# ospi_v14.net
KiCad netlist of a schematic drawn in EAGLE
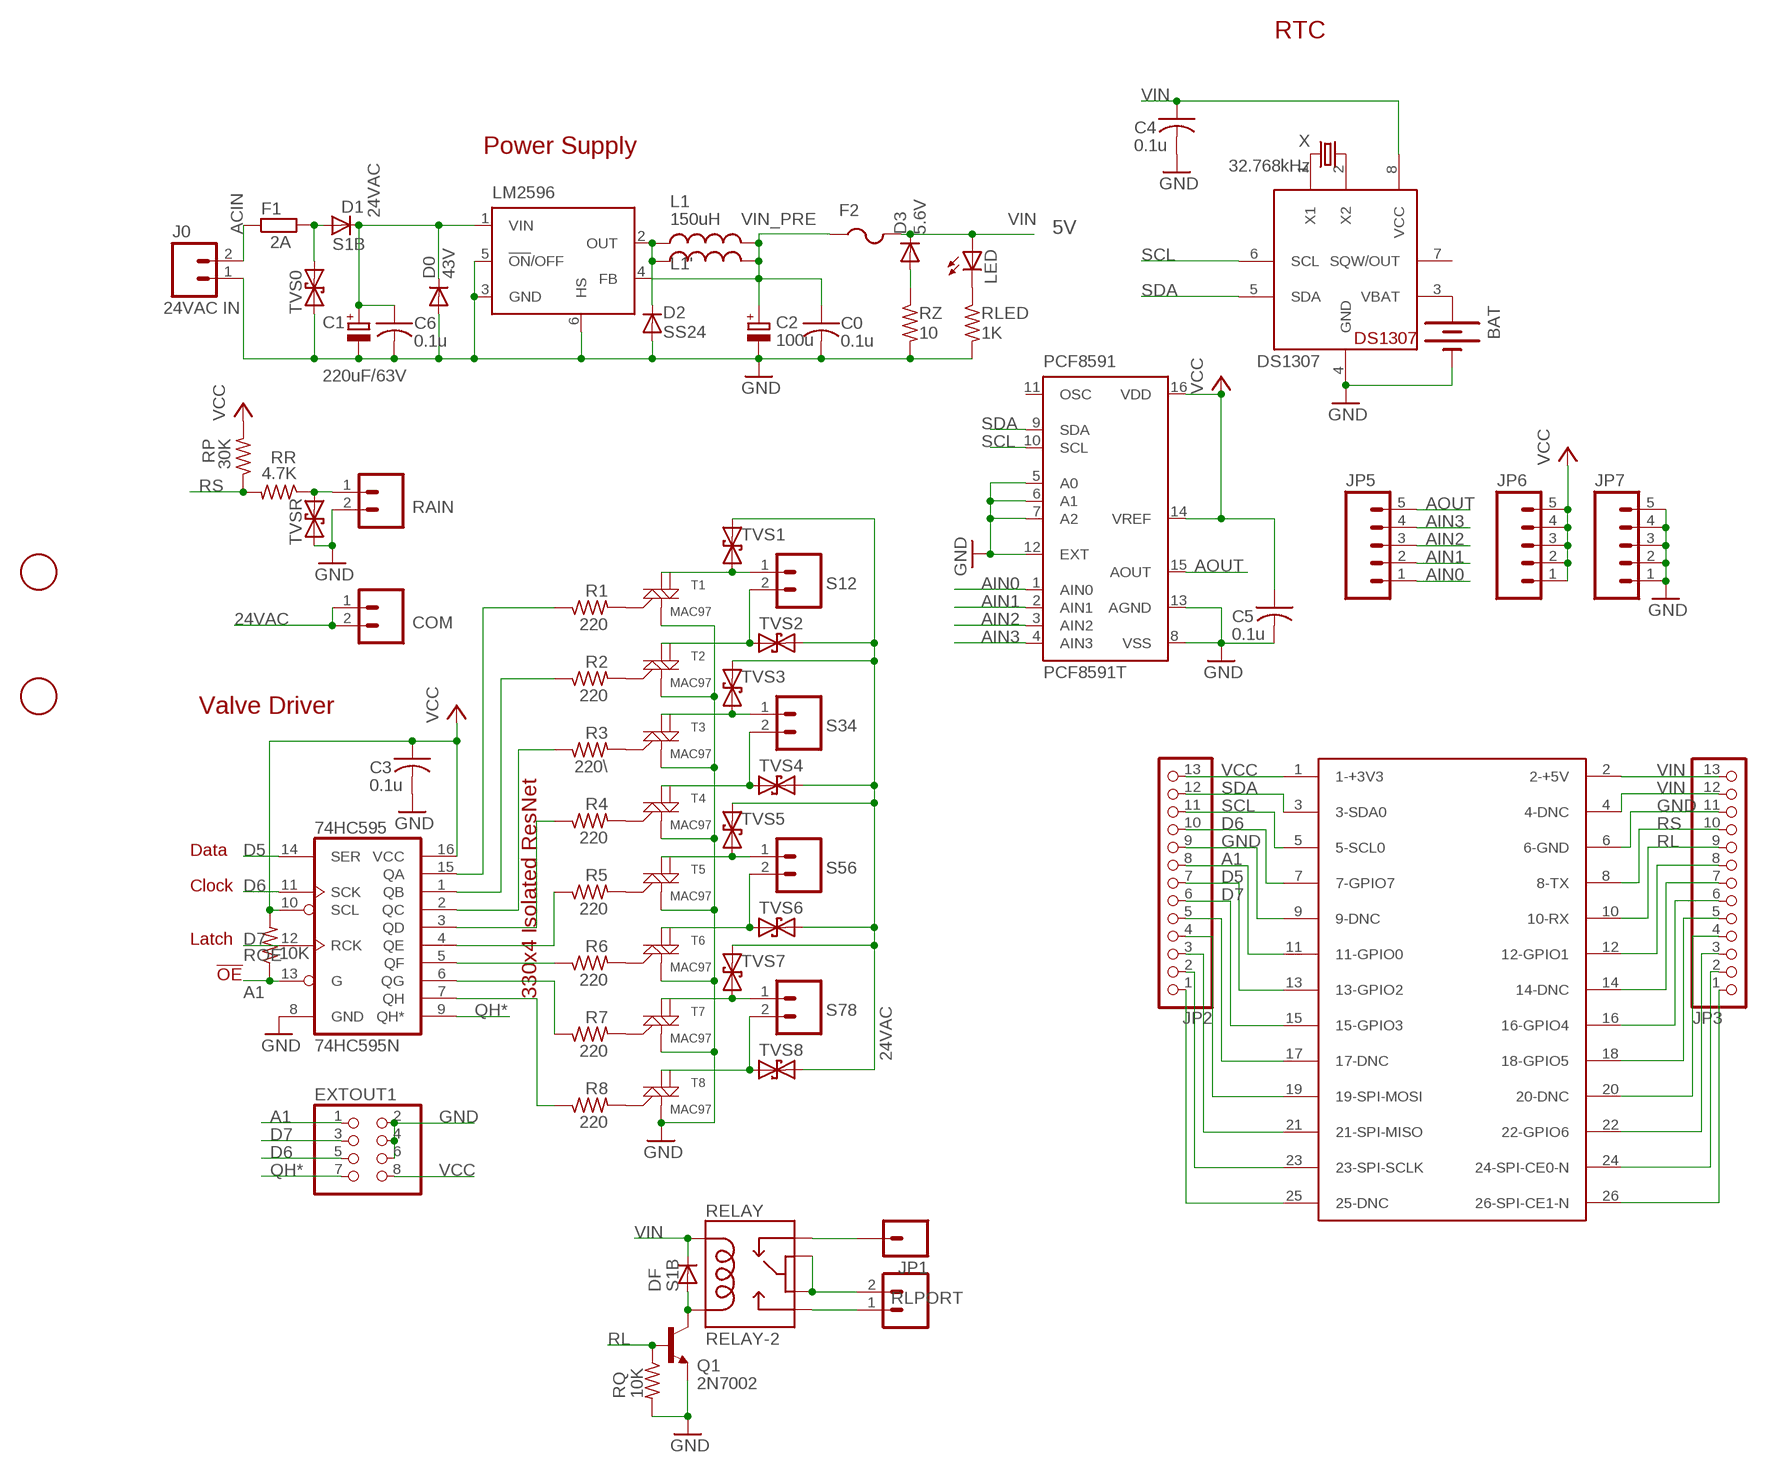
[diagram p0: schematic, sheet 1]

(export (version "E")
  (design (tool "Eeschema 10.0.6"))
  (components
    (comp (ref "74HC595")
      (value "74HC595N")
      (footprint "eagle-import:SO16")
      (libsource (lib "eagle-import") (part "74595DLS"))
    )
    (comp (ref "BAT")
      (value "BATTERYBATTERY_12MM_SMT")
      (footprint "eagle-import:BATTCON_12MM_SMT")
      (libsource (lib "eagle-import") (part "BATTERYBATTERY_12MM_SMT"))
    )
    (comp (ref "C0")
      (value "0.1u")
      (footprint "eagle-import:C0805K")
      (libsource (lib "eagle-import") (part "C-USC0805K"))
    )
    (comp (ref "C1")
      (value "220uF/63V")
      (footprint "eagle-import:E5-10,5")
      (libsource (lib "eagle-import") (part "CPOL-EUE5-10.5"))
    )
    (comp (ref "C2")
      (value "100u")
      (footprint "eagle-import:E3,5-8")
      (libsource (lib "eagle-import") (part "CPOL-EUE3.5-8"))
    )
    (comp (ref "C3")
      (value "0.1u")
      (footprint "eagle-import:C0805K")
      (libsource (lib "eagle-import") (part "C-USC0805K"))
    )
    (comp (ref "C4")
      (value "0.1u")
      (footprint "eagle-import:C0805K")
      (libsource (lib "eagle-import") (part "C-USC0805K"))
    )
    (comp (ref "C5")
      (value "0.1u")
      (footprint "eagle-import:C0805K")
      (libsource (lib "eagle-import") (part "C-USC0805K"))
    )
    (comp (ref "C6")
      (value "0.1u")
      (footprint "eagle-import:C0805K")
      (libsource (lib "eagle-import") (part "C-USC0805K"))
    )
    (comp (ref "COM")
      (value "M025MM-X")
      (footprint "eagle-import:SCREWTERMINAL-5MM-2-X")
      (libsource (lib "eagle-import") (part "M025MM-X"))
    )
    (comp (ref "D0")
      (value "43V")
      (footprint "eagle-import:MINIMELF")
      (libsource (lib "eagle-import") (part "DIODE-MINIMELF"))
    )
    (comp (ref "D1")
      (value "S1B")
      (footprint "eagle-import:DO-214AC")
      (libsource (lib "eagle-import") (part "DIODE-DO-214AC"))
    )
    (comp (ref "D2")
      (value "SS24")
      (footprint "eagle-import:SMB")
      (libsource (lib "eagle-import") (part "DIODE-SMB"))
    )
    (comp (ref "D3")
      (value "5.6V")
      (footprint "eagle-import:MINIMELF")
      (libsource (lib "eagle-import") (part "DIODE-MINIMELF"))
    )
    (comp (ref "DF")
      (value "S1B")
      (footprint "eagle-import:DO-214AC")
      (libsource (lib "eagle-import") (part "DIODE-DO-214AC"))
    )
    (comp (ref "DS1307")
      (value "DS1307")
      (footprint "eagle-import:SO08")
      (libsource (lib "eagle-import") (part "DS1307SOIC"))
    )
    (comp (ref "EXTOUT1")
      (value "PINHD-2X4/90")
      (footprint "eagle-import:2X04_90")
      (libsource (lib "eagle-import") (part "PINHD-2X4/90"))
    )
    (comp (ref "F1")
      (value "2A")
      (footprint "eagle-import:0411V")
      (libsource (lib "eagle-import") (part "R-EU_0411/3V"))
    )
    (comp (ref "F2")
      (value "PTCFUSE-1812")
      (footprint "eagle-import:1812")
      (libsource (lib "eagle-import") (part "PTCFUSE-1812"))
    )
    (comp (ref "J0")
      (value "24VAC IN")
      (footprint "eagle-import:SCREWTERMINAL-4MM-2-X")
      (libsource (lib "eagle-import") (part "M024MM-X"))
    )
    (comp (ref "JP1")
      (value "M01PTH")
      (footprint "eagle-import:1X01")
      (libsource (lib "eagle-import") (part "M01PTH"))
    )
    (comp (ref "JP2")
      (value "PINHD-1X13_BIG")
      (footprint "eagle-import:1X13-BIG")
      (libsource (lib "eagle-import") (part "PINHD-1X13_BIG"))
    )
    (comp (ref "JP3")
      (value "PINHD-1X13_BIG")
      (footprint "eagle-import:1X13-BIG")
      (libsource (lib "eagle-import") (part "PINHD-1X13_BIG"))
    )
    (comp (ref "JP5")
      (value "M05LOCK")
      (footprint "eagle-import:1X05_LOCK")
      (libsource (lib "eagle-import") (part "M05LOCK"))
    )
    (comp (ref "JP6")
      (value "M05LOCK")
      (footprint "eagle-import:1X05_LOCK")
      (libsource (lib "eagle-import") (part "M05LOCK"))
    )
    (comp (ref "JP7")
      (value "M05LOCK")
      (footprint "eagle-import:1X05_LOCK")
      (libsource (lib "eagle-import") (part "M05LOCK"))
    )
    (comp (ref "L1")
      (value "150uH")
      (footprint "eagle-import:CDRH125")
      (libsource (lib "eagle-import") (part "INDUCTORPWR"))
    )
    (comp (ref "L1'")
      (value "150uH")
      (footprint "eagle-import:0207_7")
      (libsource (lib "eagle-import") (part "L-US0207/7"))
    )
    (comp (ref "LED")
      (value "LEDCHIPLED_0805")
      (footprint "eagle-import:CHIPLED_0805")
      (libsource (lib "eagle-import") (part "LEDCHIPLED_0805"))
    )
    (comp (ref "LM2596")
      (value "LM2596S")
      (footprint "eagle-import:TO263-5")
      (fields (field (name "MF") "NATIONAL SEMICONDUCTOR") (field (name "MPN") "LM2596S-ADJ/NOPB"))
      (libsource (lib "eagle-import") (part "LM2596S"))
    )
    (comp (ref "PCF8591")
      (value "PCF8591T")
      (footprint "eagle-import:SO16W")
      (fields (field (name "MPN") "PCF8591T/2,512"))
      (libsource (lib "eagle-import") (part "PCF8591T"))
    )
    (comp (ref "Q1")
      (value "2N7002")
      (footprint "eagle-import:SOT23-3")
      (libsource (lib "eagle-import") (part "TRANSISTOR_NPNSOT23-3"))
    )
    (comp (ref "R1")
      (value "220")
      (footprint "eagle-import:R0805")
      (libsource (lib "eagle-import") (part "R-US_R0805"))
    )
    (comp (ref "R2")
      (value "220")
      (footprint "eagle-import:R0805")
      (libsource (lib "eagle-import") (part "R-US_R0805"))
    )
    (comp (ref "R3")
      (value "220\\")
      (footprint "eagle-import:R0805")
      (libsource (lib "eagle-import") (part "R-US_R0805"))
    )
    (comp (ref "R4")
      (value "220")
      (footprint "eagle-import:R0805")
      (libsource (lib "eagle-import") (part "R-US_R0805"))
    )
    (comp (ref "R5")
      (value "220")
      (footprint "eagle-import:R0805")
      (libsource (lib "eagle-import") (part "R-US_R0805"))
    )
    (comp (ref "R6")
      (value "220")
      (footprint "eagle-import:R0805")
      (libsource (lib "eagle-import") (part "R-US_R0805"))
    )
    (comp (ref "R7")
      (value "220")
      (footprint "eagle-import:R0805")
      (libsource (lib "eagle-import") (part "R-US_R0805"))
    )
    (comp (ref "R8")
      (value "220")
      (footprint "eagle-import:R0805")
      (libsource (lib "eagle-import") (part "R-US_R0805"))
    )
    (comp (ref "RAIN")
      (value "M025MM-X")
      (footprint "eagle-import:SCREWTERMINAL-5MM-2-X")
      (libsource (lib "eagle-import") (part "M025MM-X"))
    )
    (comp (ref "RELAY")
      (value "RELAY-2")
      (footprint "eagle-import:RELAY-HK4100F")
      (libsource (lib "eagle-import") (part "RELAY-2"))
    )
    (comp (ref "RLED")
      (value "1K")
      (footprint "eagle-import:R0805")
      (libsource (lib "eagle-import") (part "R-US_R0805"))
    )
    (comp (ref "RLPORT")
      (value "M025MM")
      (footprint "eagle-import:SCREWTERMINAL-5MM-2")
      (libsource (lib "eagle-import") (part "M025MM"))
    )
    (comp (ref "ROE")
      (value "10K")
      (footprint "eagle-import:R0805")
      (libsource (lib "eagle-import") (part "R-US_R0805"))
    )
    (comp (ref "RP")
      (value "30K")
      (footprint "eagle-import:R0805")
      (libsource (lib "eagle-import") (part "R-US_R0805"))
    )
    (comp (ref "RQ")
      (value "10K")
      (footprint "eagle-import:R0805")
      (libsource (lib "eagle-import") (part "R-US_R0805"))
    )
    (comp (ref "RR")
      (value "4.7K")
      (footprint "eagle-import:R0805")
      (libsource (lib "eagle-import") (part "R-US_R0805"))
    )
    (comp (ref "RZ")
      (value "10")
      (footprint "eagle-import:R0805")
      (libsource (lib "eagle-import") (part "R-US_R0805"))
    )
    (comp (ref "S12")
      (value "M025MM-X")
      (footprint "eagle-import:SCREWTERMINAL-5MM-2-X")
      (libsource (lib "eagle-import") (part "M025MM-X"))
    )
    (comp (ref "S34")
      (value "M025MM-X")
      (footprint "eagle-import:SCREWTERMINAL-5MM-2-X")
      (libsource (lib "eagle-import") (part "M025MM-X"))
    )
    (comp (ref "S56")
      (value "M025MM-X")
      (footprint "eagle-import:SCREWTERMINAL-5MM-2-X")
      (libsource (lib "eagle-import") (part "M025MM-X"))
    )
    (comp (ref "S78")
      (value "M025MM-X")
      (footprint "eagle-import:SCREWTERMINAL-5MM-2-X")
      (libsource (lib "eagle-import") (part "M025MM-X"))
    )
    (comp (ref "T1")
      (value "MAC97")
      (footprint "eagle-import:SOT223")
      (libsource (lib "eagle-import") (part "MAC97SOT223"))
    )
    (comp (ref "T2")
      (value "MAC97")
      (footprint "eagle-import:SOT223")
      (libsource (lib "eagle-import") (part "MAC97SOT223"))
    )
    (comp (ref "T3")
      (value "MAC97")
      (footprint "eagle-import:SOT223")
      (libsource (lib "eagle-import") (part "MAC97SOT223"))
    )
    (comp (ref "T4")
      (value "MAC97")
      (footprint "eagle-import:SOT223")
      (libsource (lib "eagle-import") (part "MAC97SOT223"))
    )
    (comp (ref "T5")
      (value "MAC97")
      (footprint "eagle-import:SOT223")
      (libsource (lib "eagle-import") (part "MAC97SOT223"))
    )
    (comp (ref "T6")
      (value "MAC97")
      (footprint "eagle-import:SOT223")
      (libsource (lib "eagle-import") (part "MAC97SOT223"))
    )
    (comp (ref "T7")
      (value "MAC97")
      (footprint "eagle-import:SOT223")
      (libsource (lib "eagle-import") (part "MAC97SOT223"))
    )
    (comp (ref "T8")
      (value "MAC97")
      (footprint "eagle-import:SOT223")
      (libsource (lib "eagle-import") (part "MAC97SOT223"))
    )
    (comp (ref "TVS0")
      (value "TVSSMB")
      (footprint "eagle-import:SMB")
      (libsource (lib "eagle-import") (part "TVSSMB"))
    )
    (comp (ref "TVS1")
      (value "TVSSMB")
      (footprint "eagle-import:SMB")
      (libsource (lib "eagle-import") (part "TVSSMB"))
    )
    (comp (ref "TVS2")
      (value "TVSSMB")
      (footprint "eagle-import:SMB")
      (libsource (lib "eagle-import") (part "TVSSMB"))
    )
    (comp (ref "TVS3")
      (value "TVSSMB")
      (footprint "eagle-import:SMB")
      (libsource (lib "eagle-import") (part "TVSSMB"))
    )
    (comp (ref "TVS4")
      (value "TVSSMB")
      (footprint "eagle-import:SMB")
      (libsource (lib "eagle-import") (part "TVSSMB"))
    )
    (comp (ref "TVS5")
      (value "TVSSMB")
      (footprint "eagle-import:SMB")
      (libsource (lib "eagle-import") (part "TVSSMB"))
    )
    (comp (ref "TVS6")
      (value "TVSSMB")
      (footprint "eagle-import:SMB")
      (libsource (lib "eagle-import") (part "TVSSMB"))
    )
    (comp (ref "TVS7")
      (value "TVSSMB")
      (footprint "eagle-import:SMB")
      (libsource (lib "eagle-import") (part "TVSSMB"))
    )
    (comp (ref "TVS8")
      (value "TVSSMB")
      (footprint "eagle-import:SMB")
      (libsource (lib "eagle-import") (part "TVSSMB"))
    )
    (comp (ref "TVSR")
      (value "TVSSMB")
      (footprint "eagle-import:SMB")
      (libsource (lib "eagle-import") (part "TVSSMB"))
    )
    (comp (ref "U$1")
      (value "FIDUCIAL")
      (footprint "eagle-import:FIDUCIAL_1MM")
      (libsource (lib "eagle-import") (part "FIDUCIAL"))
    )
    (comp (ref "U$2")
      (value "RASPBERRY-PI")
      (footprint "eagle-import:RASPBERRY-PI")
      (libsource (lib "eagle-import") (part "RASPBERRY-PI"))
    )
    (comp (ref "U$3")
      (value "FIDUCIAL")
      (footprint "eagle-import:FIDUCIAL_1MM")
      (libsource (lib "eagle-import") (part "FIDUCIAL"))
    )
    (comp (ref "X")
      (value "32.768kHz")
      (footprint "eagle-import:TC38H")
      (libsource (lib "eagle-import") (part "CRYSTALTC38H"))
    )
  )
  (nets
    (net (code "1") (name "/24VAC") (class "Default")
      (node (ref "COM") (pin "1") (pinfunction "1_1") (pintype "passive"))
      (node (ref "COM") (pin "2") (pinfunction "2_2") (pintype "passive"))
      (node (ref "D1") (pin "A") (pinfunction "A_A") (pintype "passive"))
      (node (ref "F1") (pin "2") (pinfunction "2_2") (pintype "passive"))
      (node (ref "TVS0") (pin "C") (pinfunction "C_C") (pintype "passive"))
      (node (ref "TVS1") (pin "C") (pinfunction "C_C") (pintype "passive"))
      (node (ref "TVS2") (pin "C") (pinfunction "C_C") (pintype "passive"))
      (node (ref "TVS3") (pin "C") (pinfunction "C_C") (pintype "passive"))
      (node (ref "TVS4") (pin "C") (pinfunction "C_C") (pintype "passive"))
      (node (ref "TVS5") (pin "C") (pinfunction "C_C") (pintype "passive"))
      (node (ref "TVS6") (pin "C") (pinfunction "C_C") (pintype "passive"))
      (node (ref "TVS7") (pin "C") (pinfunction "C_C") (pintype "passive"))
      (node (ref "TVS8") (pin "C") (pinfunction "C_C") (pintype "passive"))
    )
    (net (code "2") (name "/A1") (class "Default")
      (node (ref "74HC595") (pin "13") (pinfunction "G_13") (pintype "input"))
      (node (ref "EXTOUT1") (pin "1") (pinfunction "1_1") (pintype "passive"))
      (node (ref "JP2") (pin "8") (pinfunction "8_8") (pintype "passive"))
      (node (ref "ROE") (pin "1") (pinfunction "1_1") (pintype "passive"))
      (node (ref "U$2") (pin "11") (pinfunction "11-GPIO0_11") (pintype "bidirectional"))
    )
    (net (code "3") (name "/ACIN") (class "Default")
      (node (ref "F1") (pin "1") (pinfunction "1_1") (pintype "passive"))
      (node (ref "J0") (pin "2") (pinfunction "2_2") (pintype "passive"))
    )
    (net (code "4") (name "/AIN0") (class "Default")
      (node (ref "JP5") (pin "1") (pinfunction "1_1") (pintype "passive"))
      (node (ref "PCF8591") (pin "1") (pinfunction "AIN0_1") (pintype "input"))
    )
    (net (code "5") (name "/AIN1") (class "Default")
      (node (ref "JP5") (pin "2") (pinfunction "2_2") (pintype "passive"))
      (node (ref "PCF8591") (pin "2") (pinfunction "AIN1_2") (pintype "input"))
    )
    (net (code "6") (name "/AIN2") (class "Default")
      (node (ref "JP5") (pin "3") (pinfunction "3_3") (pintype "passive"))
      (node (ref "PCF8591") (pin "3") (pinfunction "AIN2_3") (pintype "input"))
    )
    (net (code "7") (name "/AIN3") (class "Default")
      (node (ref "JP5") (pin "4") (pinfunction "4_4") (pintype "passive"))
      (node (ref "PCF8591") (pin "4") (pinfunction "AIN3_4") (pintype "input"))
    )
    (net (code "8") (name "/AOUT") (class "Default")
      (node (ref "JP5") (pin "5") (pinfunction "5_5") (pintype "passive"))
      (node (ref "PCF8591") (pin "15") (pinfunction "AOUT_15") (pintype "output"))
    )
    (net (code "9") (name "/D5") (class "Default")
      (node (ref "74HC595") (pin "14") (pinfunction "SER_14") (pintype "input"))
      (node (ref "JP2") (pin "7") (pinfunction "7_7") (pintype "passive"))
      (node (ref "U$2") (pin "13") (pinfunction "13-GPIO2_13") (pintype "bidirectional"))
    )
    (net (code "10") (name "/D6") (class "Default")
      (node (ref "74HC595") (pin "11") (pinfunction "SCK_11") (pintype "input"))
      (node (ref "EXTOUT1") (pin "5") (pinfunction "5_5") (pintype "passive"))
      (node (ref "JP2") (pin "10") (pinfunction "10_10") (pintype "passive"))
      (node (ref "U$2") (pin "7") (pinfunction "7-GPIO7_7") (pintype "bidirectional"))
    )
    (net (code "11") (name "/D7") (class "Default")
      (node (ref "74HC595") (pin "12") (pinfunction "RCK_12") (pintype "input"))
      (node (ref "EXTOUT1") (pin "3") (pinfunction "3_3") (pintype "passive"))
      (node (ref "JP2") (pin "6") (pinfunction "6_6") (pintype "passive"))
      (node (ref "U$2") (pin "15") (pinfunction "15-GPIO3_15") (pintype "bidirectional"))
    )
    (net (code "12") (name "/QH*") (class "Default")
      (node (ref "74HC595") (pin "9") (pinfunction "QH*_9") (pintype "tri_state"))
      (node (ref "EXTOUT1") (pin "7") (pinfunction "7_7") (pintype "passive"))
    )
    (net (code "13") (name "/RL") (class "Default")
      (node (ref "JP3") (pin "9") (pinfunction "9_9") (pintype "passive"))
      (node (ref "Q1") (pin "1") (pinfunction "B_1") (pintype "passive"))
      (node (ref "RQ") (pin "1") (pinfunction "1_1") (pintype "passive"))
      (node (ref "U$2") (pin "10") (pinfunction "10-RX_10") (pintype "bidirectional"))
    )
    (net (code "14") (name "/RS") (class "Default")
      (node (ref "JP3") (pin "10") (pinfunction "10_10") (pintype "passive"))
      (node (ref "RP") (pin "1") (pinfunction "1_1") (pintype "passive"))
      (node (ref "RR") (pin "2") (pinfunction "2_2") (pintype "passive"))
      (node (ref "U$2") (pin "8") (pinfunction "8-TX_8") (pintype "bidirectional"))
    )
    (net (code "15") (name "/SCL") (class "Default")
      (node (ref "DS1307") (pin "6") (pinfunction "SCL_6") (pintype "bidirectional"))
      (node (ref "JP2") (pin "11") (pinfunction "11_11") (pintype "passive"))
      (node (ref "PCF8591") (pin "10") (pinfunction "SCL_10") (pintype "input"))
      (node (ref "U$2") (pin "5") (pinfunction "5-SCL0_5") (pintype "bidirectional"))
    )
    (net (code "16") (name "/SDA") (class "Default")
      (node (ref "DS1307") (pin "5") (pinfunction "SDA_5") (pintype "bidirectional"))
      (node (ref "JP2") (pin "12") (pinfunction "12_12") (pintype "passive"))
      (node (ref "PCF8591") (pin "9") (pinfunction "SDA_9") (pintype "bidirectional"))
      (node (ref "U$2") (pin "3") (pinfunction "3-SDA0_3") (pintype "bidirectional"))
    )
    (net (code "17") (name "/VIN") (class "Default")
      (node (ref "C4") (pin "1") (pinfunction "1_1") (pintype "passive"))
      (node (ref "D3") (pin "C") (pinfunction "C_C") (pintype "passive"))
      (node (ref "DF") (pin "C") (pinfunction "C_C") (pintype "passive"))
      (node (ref "DS1307") (pin "8") (pinfunction "VCC_8") (pintype "power_in"))
      (node (ref "F2") (pin "2") (pinfunction "2_2") (pintype "passive"))
      (node (ref "JP3") (pin "12") (pinfunction "12_12") (pintype "passive"))
      (node (ref "JP3") (pin "13") (pinfunction "13_13") (pintype "passive"))
      (node (ref "LED") (pin "A") (pinfunction "A_A") (pintype "passive"))
      (node (ref "RELAY") (pin "2") (pinfunction "2_2") (pintype "bidirectional"))
      (node (ref "U$2") (pin "2") (pinfunction "2-+5V_2") (pintype "bidirectional"))
      (node (ref "U$2") (pin "4") (pinfunction "4-DNC_4") (pintype "bidirectional"))
    )
    (net (code "18") (name "/VIN_PRE") (class "Default")
      (node (ref "C0") (pin "1") (pinfunction "1_1") (pintype "passive"))
      (node (ref "C2") (pin "+") (pinfunction "+_+") (pintype "passive"))
      (node (ref "F2") (pin "1") (pinfunction "1_1") (pintype "passive"))
      (node (ref "L1") (pin "2") (pinfunction "2_2") (pintype "passive"))
      (node (ref "L1'") (pin "2") (pinfunction "2_2") (pintype "passive"))
      (node (ref "LM2596") (pin "4") (pinfunction "FB_4") (pintype "input"))
    )
    (net (code "19") (name "GND") (class "Default")
      (node (ref "74HC595") (pin "8") (pinfunction "GND_8") (pintype "power_in"))
      (node (ref "BAT") (pin "P$1") (pinfunction "-_P$1") (pintype "power_in"))
      (node (ref "C0") (pin "2") (pinfunction "2_2") (pintype "passive"))
      (node (ref "C1") (pin "-") (pinfunction "-_-") (pintype "passive"))
      (node (ref "C2") (pin "-") (pinfunction "-_-") (pintype "passive"))
      (node (ref "C3") (pin "2") (pinfunction "2_2") (pintype "passive"))
      (node (ref "C4") (pin "2") (pinfunction "2_2") (pintype "passive"))
      (node (ref "C5") (pin "2") (pinfunction "2_2") (pintype "passive"))
      (node (ref "C6") (pin "2") (pinfunction "2_2") (pintype "passive"))
      (node (ref "D0") (pin "A") (pinfunction "A_A") (pintype "passive"))
      (node (ref "D2") (pin "A") (pinfunction "A_A") (pintype "passive"))
      (node (ref "DS1307") (pin "4") (pinfunction "GND_4") (pintype "power_in"))
      (node (ref "EXTOUT1") (pin "2") (pinfunction "2_2") (pintype "passive"))
      (node (ref "EXTOUT1") (pin "4") (pinfunction "4_4") (pintype "passive"))
      (node (ref "EXTOUT1") (pin "6") (pinfunction "6_6") (pintype "passive"))
      (node (ref "J0") (pin "1") (pinfunction "1_1") (pintype "passive"))
      (node (ref "JP2") (pin "9") (pinfunction "9_9") (pintype "passive"))
      (node (ref "JP3") (pin "11") (pinfunction "11_11") (pintype "passive"))
      (node (ref "JP7") (pin "1") (pinfunction "1_1") (pintype "passive"))
      (node (ref "JP7") (pin "2") (pinfunction "2_2") (pintype "passive"))
      (node (ref "JP7") (pin "3") (pinfunction "3_3") (pintype "passive"))
      (node (ref "JP7") (pin "4") (pinfunction "4_4") (pintype "passive"))
      (node (ref "JP7") (pin "5") (pinfunction "5_5") (pintype "passive"))
      (node (ref "LM2596") (pin "3") (pinfunction "GND_3") (pintype "power_in"))
      (node (ref "LM2596") (pin "5") (pinfunction "~{ON}/OFF_5") (pintype "input"))
      (node (ref "LM2596") (pin "6") (pinfunction "HS_6") (pintype "power_in"))
      (node (ref "PCF8591") (pin "12") (pinfunction "EXT_12") (pintype "input"))
      (node (ref "PCF8591") (pin "13") (pinfunction "AGND_13") (pintype "power_in"))
      (node (ref "PCF8591") (pin "5") (pinfunction "A0_5") (pintype "input"))
      (node (ref "PCF8591") (pin "6") (pinfunction "A1_6") (pintype "input"))
      (node (ref "PCF8591") (pin "7") (pinfunction "A2_7") (pintype "input"))
      (node (ref "PCF8591") (pin "8") (pinfunction "VSS_8") (pintype "power_in"))
      (node (ref "Q1") (pin "2") (pinfunction "E_2") (pintype "passive"))
      (node (ref "RAIN") (pin "2") (pinfunction "2_2") (pintype "passive"))
      (node (ref "RLED") (pin "2") (pinfunction "2_2") (pintype "passive"))
      (node (ref "RQ") (pin "2") (pinfunction "2_2") (pintype "passive"))
      (node (ref "RZ") (pin "2") (pinfunction "2_2") (pintype "passive"))
      (node (ref "T1") (pin "1") (pinfunction "M1_1") (pintype "bidirectional"))
      (node (ref "T2") (pin "1") (pinfunction "M1_1") (pintype "bidirectional"))
      (node (ref "T3") (pin "1") (pinfunction "M1_1") (pintype "bidirectional"))
      (node (ref "T4") (pin "1") (pinfunction "M1_1") (pintype "bidirectional"))
      (node (ref "T5") (pin "1") (pinfunction "M1_1") (pintype "bidirectional"))
      (node (ref "T6") (pin "1") (pinfunction "M1_1") (pintype "bidirectional"))
      (node (ref "T7") (pin "1") (pinfunction "M1_1") (pintype "bidirectional"))
      (node (ref "T8") (pin "1") (pinfunction "M1_1") (pintype "bidirectional"))
      (node (ref "TVS0") (pin "A") (pinfunction "A_A") (pintype "passive"))
      (node (ref "TVSR") (pin "A") (pinfunction "A_A") (pintype "passive"))
      (node (ref "U$2") (pin "6") (pinfunction "6-GND_6") (pintype "bidirectional"))
      (node (ref "U$2") (pin "9") (pinfunction "9-DNC_9") (pintype "bidirectional"))
    )
    (net (code "20") (name "Net-(74HC595-QA)") (class "Default")
      (node (ref "74HC595") (pin "15") (pinfunction "QA_15") (pintype "tri_state"))
      (node (ref "R1") (pin "1") (pinfunction "1_1") (pintype "passive"))
    )
    (net (code "21") (name "Net-(74HC595-QB)") (class "Default")
      (node (ref "74HC595") (pin "1") (pinfunction "QB_1") (pintype "tri_state"))
      (node (ref "R2") (pin "1") (pinfunction "1_1") (pintype "passive"))
    )
    (net (code "22") (name "Net-(74HC595-QC)") (class "Default")
      (node (ref "74HC595") (pin "2") (pinfunction "QC_2") (pintype "tri_state"))
      (node (ref "R3") (pin "1") (pinfunction "1_1") (pintype "passive"))
    )
    (net (code "23") (name "Net-(74HC595-QD)") (class "Default")
      (node (ref "74HC595") (pin "3") (pinfunction "QD_3") (pintype "tri_state"))
      (node (ref "R4") (pin "1") (pinfunction "1_1") (pintype "passive"))
    )
    (net (code "24") (name "Net-(74HC595-QE)") (class "Default")
      (node (ref "74HC595") (pin "4") (pinfunction "QE_4") (pintype "tri_state"))
      (node (ref "R5") (pin "1") (pinfunction "1_1") (pintype "passive"))
    )
    (net (code "25") (name "Net-(74HC595-QF)") (class "Default")
      (node (ref "74HC595") (pin "5") (pinfunction "QF_5") (pintype "tri_state"))
      (node (ref "R6") (pin "1") (pinfunction "1_1") (pintype "passive"))
    )
    (net (code "26") (name "Net-(74HC595-QG)") (class "Default")
      (node (ref "74HC595") (pin "6") (pinfunction "QG_6") (pintype "tri_state"))
      (node (ref "R7") (pin "1") (pinfunction "1_1") (pintype "passive"))
    )
    (net (code "27") (name "Net-(74HC595-QH)") (class "Default")
      (node (ref "74HC595") (pin "7") (pinfunction "QH_7") (pintype "tri_state"))
      (node (ref "R8") (pin "1") (pinfunction "1_1") (pintype "passive"))
    )
    (net (code "28") (name "Net-(BAT-+)") (class "Default")
      (node (ref "BAT") (pin "P$2") (pinfunction "+_P$2") (pintype "power_in"))
      (node (ref "DS1307") (pin "3") (pinfunction "VBAT_3") (pintype "power_in"))
    )
    (net (code "29") (name "Net-(D3-PadA)") (class "Default")
      (node (ref "D3") (pin "A") (pinfunction "A_A") (pintype "passive"))
      (node (ref "RZ") (pin "1") (pinfunction "1_1") (pintype "passive"))
    )
    (net (code "30") (name "Net-(DS1307-X1)") (class "Default")
      (node (ref "DS1307") (pin "1") (pinfunction "X1_1") (pintype "passive"))
      (node (ref "X") (pin "2") (pinfunction "2_2") (pintype "passive"))
    )
    (net (code "31") (name "Net-(DS1307-X2)") (class "Default")
      (node (ref "DS1307") (pin "2") (pinfunction "X2_2") (pintype "passive"))
      (node (ref "X") (pin "1") (pinfunction "1_1") (pintype "passive"))
    )
    (net (code "32") (name "Net-(JP1-Pad1)") (class "Default")
      (node (ref "JP1") (pin "1") (pinfunction "1_1") (pintype "passive"))
      (node (ref "RELAY") (pin "1") (pinfunction "1_1") (pintype "bidirectional"))
    )
    (net (code "33") (name "Net-(LED-PadC)") (class "Default")
      (node (ref "LED") (pin "C") (pinfunction "C_C") (pintype "passive"))
      (node (ref "RLED") (pin "1") (pinfunction "1_1") (pintype "passive"))
    )
    (net (code "34") (name "Net-(LM2596-OUT)") (class "Default")
      (node (ref "D2") (pin "C") (pinfunction "C_C") (pintype "passive"))
      (node (ref "L1") (pin "1") (pinfunction "1_1") (pintype "passive"))
      (node (ref "L1'") (pin "1") (pinfunction "1_1") (pintype "passive"))
      (node (ref "LM2596") (pin "2") (pinfunction "OUT_2") (pintype "output"))
    )
    (net (code "35") (name "Net-(LM2596-VIN)") (class "Default")
      (node (ref "C1") (pin "+") (pinfunction "+_+") (pintype "passive"))
      (node (ref "C6") (pin "1") (pinfunction "1_1") (pintype "passive"))
      (node (ref "D0") (pin "C") (pinfunction "C_C") (pintype "passive"))
      (node (ref "D1") (pin "C") (pinfunction "C_C") (pintype "passive"))
      (node (ref "LM2596") (pin "1") (pinfunction "VIN_1") (pintype "input"))
    )
    (net (code "36") (name "Net-(Q1-C)") (class "Default")
      (node (ref "DF") (pin "A") (pinfunction "A_A") (pintype "passive"))
      (node (ref "Q1") (pin "3") (pinfunction "C_3") (pintype "passive"))
      (node (ref "RELAY") (pin "9") (pinfunction "9_9") (pintype "bidirectional"))
    )
    (net (code "37") (name "Net-(RAIN-Pad1)") (class "Default")
      (node (ref "RAIN") (pin "1") (pinfunction "1_1") (pintype "passive"))
      (node (ref "RR") (pin "1") (pinfunction "1_1") (pintype "passive"))
      (node (ref "TVSR") (pin "C") (pinfunction "C_C") (pintype "passive"))
    )
    (net (code "38") (name "Net-(RELAY-Pad5)") (class "Default")
      (node (ref "RELAY") (pin "5") (pinfunction "5_5") (pintype "bidirectional"))
      (node (ref "RELAY") (pin "6") (pinfunction "6_6") (pintype "bidirectional"))
      (node (ref "RLPORT") (pin "2") (pinfunction "2_2") (pintype "passive"))
    )
    (net (code "39") (name "Net-(RELAY-Pad10)") (class "Default")
      (node (ref "RELAY") (pin "10") (pinfunction "10_10") (pintype "bidirectional"))
      (node (ref "RLPORT") (pin "1") (pinfunction "1_1") (pintype "passive"))
    )
    (net (code "40") (name "Net-(T1-G)") (class "Default")
      (node (ref "R1") (pin "2") (pinfunction "2_2") (pintype "passive"))
      (node (ref "T1") (pin "3") (pinfunction "G_3") (pintype "bidirectional"))
    )
    (net (code "41") (name "Net-(T1-M2)") (class "Default")
      (node (ref "S12") (pin "1") (pinfunction "1_1") (pintype "passive"))
      (node (ref "T1") (pin "2") (pinfunction "M2_2") (pintype "bidirectional"))
      (node (ref "TVS1") (pin "A") (pinfunction "A_A") (pintype "passive"))
    )
    (net (code "42") (name "Net-(T2-G)") (class "Default")
      (node (ref "R2") (pin "2") (pinfunction "2_2") (pintype "passive"))
      (node (ref "T2") (pin "3") (pinfunction "G_3") (pintype "bidirectional"))
    )
    (net (code "43") (name "Net-(T2-M2)") (class "Default")
      (node (ref "S12") (pin "2") (pinfunction "2_2") (pintype "passive"))
      (node (ref "T2") (pin "2") (pinfunction "M2_2") (pintype "bidirectional"))
      (node (ref "TVS2") (pin "A") (pinfunction "A_A") (pintype "passive"))
    )
    (net (code "44") (name "Net-(T3-G)") (class "Default")
      (node (ref "R3") (pin "2") (pinfunction "2_2") (pintype "passive"))
      (node (ref "T3") (pin "3") (pinfunction "G_3") (pintype "bidirectional"))
    )
    (net (code "45") (name "Net-(T3-M2)") (class "Default")
      (node (ref "S34") (pin "1") (pinfunction "1_1") (pintype "passive"))
      (node (ref "T3") (pin "2") (pinfunction "M2_2") (pintype "bidirectional"))
      (node (ref "TVS3") (pin "A") (pinfunction "A_A") (pintype "passive"))
    )
    (net (code "46") (name "Net-(T4-G)") (class "Default")
      (node (ref "R4") (pin "2") (pinfunction "2_2") (pintype "passive"))
      (node (ref "T4") (pin "3") (pinfunction "G_3") (pintype "bidirectional"))
    )
    (net (code "47") (name "Net-(T4-M2)") (class "Default")
      (node (ref "S34") (pin "2") (pinfunction "2_2") (pintype "passive"))
      (node (ref "T4") (pin "2") (pinfunction "M2_2") (pintype "bidirectional"))
      (node (ref "TVS4") (pin "A") (pinfunction "A_A") (pintype "passive"))
    )
    (net (code "48") (name "Net-(T5-G)") (class "Default")
      (node (ref "R5") (pin "2") (pinfunction "2_2") (pintype "passive"))
      (node (ref "T5") (pin "3") (pinfunction "G_3") (pintype "bidirectional"))
    )
    (net (code "49") (name "Net-(T5-M2)") (class "Default")
      (node (ref "S56") (pin "1") (pinfunction "1_1") (pintype "passive"))
      (node (ref "T5") (pin "2") (pinfunction "M2_2") (pintype "bidirectional"))
      (node (ref "TVS5") (pin "A") (pinfunction "A_A") (pintype "passive"))
    )
    (net (code "50") (name "Net-(T6-G)") (class "Default")
      (node (ref "R6") (pin "2") (pinfunction "2_2") (pintype "passive"))
      (node (ref "T6") (pin "3") (pinfunction "G_3") (pintype "bidirectional"))
    )
    (net (code "51") (name "Net-(T6-M2)") (class "Default")
      (node (ref "S56") (pin "2") (pinfunction "2_2") (pintype "passive"))
      (node (ref "T6") (pin "2") (pinfunction "M2_2") (pintype "bidirectional"))
      (node (ref "TVS6") (pin "A") (pinfunction "A_A") (pintype "passive"))
    )
    (net (code "52") (name "Net-(T7-G)") (class "Default")
      (node (ref "R7") (pin "2") (pinfunction "2_2") (pintype "passive"))
      (node (ref "T7") (pin "3") (pinfunction "G_3") (pintype "bidirectional"))
    )
    (net (code "53") (name "Net-(T7-M2)") (class "Default")
      (node (ref "S78") (pin "1") (pinfunction "1_1") (pintype "passive"))
      (node (ref "T7") (pin "2") (pinfunction "M2_2") (pintype "bidirectional"))
      (node (ref "TVS7") (pin "A") (pinfunction "A_A") (pintype "passive"))
    )
    (net (code "54") (name "Net-(T8-G)") (class "Default")
      (node (ref "R8") (pin "2") (pinfunction "2_2") (pintype "passive"))
      (node (ref "T8") (pin "3") (pinfunction "G_3") (pintype "bidirectional"))
    )
    (net (code "55") (name "Net-(T8-M2)") (class "Default")
      (node (ref "S78") (pin "2") (pinfunction "2_2") (pintype "passive"))
      (node (ref "T8") (pin "2") (pinfunction "M2_2") (pintype "bidirectional"))
      (node (ref "TVS8") (pin "A") (pinfunction "A_A") (pintype "passive"))
    )
    (net (code "56") (name "Net-(U$2-12-GPIO1)") (class "Default")
      (node (ref "JP3") (pin "8") (pinfunction "8_8") (pintype "passive"))
      (node (ref "U$2") (pin "12") (pinfunction "12-GPIO1_12") (pintype "bidirectional"))
    )
    (net (code "57") (name "Net-(U$2-14-DNC)") (class "Default")
      (node (ref "JP3") (pin "7") (pinfunction "7_7") (pintype "passive"))
      (node (ref "U$2") (pin "14") (pinfunction "14-DNC_14") (pintype "bidirectional"))
    )
    (net (code "58") (name "Net-(U$2-16-GPIO4)") (class "Default")
      (node (ref "JP3") (pin "6") (pinfunction "6_6") (pintype "passive"))
      (node (ref "U$2") (pin "16") (pinfunction "16-GPIO4_16") (pintype "bidirectional"))
    )
    (net (code "59") (name "Net-(U$2-17-DNC)") (class "Default")
      (node (ref "JP2") (pin "5") (pinfunction "5_5") (pintype "passive"))
      (node (ref "U$2") (pin "17") (pinfunction "17-DNC_17") (pintype "bidirectional"))
    )
    (net (code "60") (name "Net-(U$2-18-GPIO5)") (class "Default")
      (node (ref "JP3") (pin "5") (pinfunction "5_5") (pintype "passive"))
      (node (ref "U$2") (pin "18") (pinfunction "18-GPIO5_18") (pintype "bidirectional"))
    )
    (net (code "61") (name "Net-(U$2-19-SPI-MOSI)") (class "Default")
      (node (ref "JP2") (pin "4") (pinfunction "4_4") (pintype "passive"))
      (node (ref "U$2") (pin "19") (pinfunction "19-SPI-MOSI_19") (pintype "bidirectional"))
    )
    (net (code "62") (name "Net-(U$2-20-DNC)") (class "Default")
      (node (ref "JP3") (pin "4") (pinfunction "4_4") (pintype "passive"))
      (node (ref "U$2") (pin "20") (pinfunction "20-DNC_20") (pintype "bidirectional"))
    )
    (net (code "63") (name "Net-(U$2-21-SPI-MISO)") (class "Default")
      (node (ref "JP2") (pin "3") (pinfunction "3_3") (pintype "passive"))
      (node (ref "U$2") (pin "21") (pinfunction "21-SPI-MISO_21") (pintype "bidirectional"))
    )
    (net (code "64") (name "Net-(U$2-22-GPIO6)") (class "Default")
      (node (ref "JP3") (pin "3") (pinfunction "3_3") (pintype "passive"))
      (node (ref "U$2") (pin "22") (pinfunction "22-GPIO6_22") (pintype "bidirectional"))
    )
    (net (code "65") (name "Net-(U$2-23-SPI-SCLK)") (class "Default")
      (node (ref "JP2") (pin "2") (pinfunction "2_2") (pintype "passive"))
      (node (ref "U$2") (pin "23") (pinfunction "23-SPI-SCLK_23") (pintype "bidirectional"))
    )
    (net (code "66") (name "Net-(U$2-24-SPI-CE0-N)") (class "Default")
      (node (ref "JP3") (pin "2") (pinfunction "2_2") (pintype "passive"))
      (node (ref "U$2") (pin "24") (pinfunction "24-SPI-CE0-N_24") (pintype "bidirectional"))
    )
    (net (code "67") (name "Net-(U$2-25-DNC)") (class "Default")
      (node (ref "JP2") (pin "1") (pinfunction "1_1") (pintype "passive"))
      (node (ref "U$2") (pin "25") (pinfunction "25-DNC_25") (pintype "bidirectional"))
    )
    (net (code "68") (name "Net-(U$2-26-SPI-CE1-N)") (class "Default")
      (node (ref "JP3") (pin "1") (pinfunction "1_1") (pintype "passive"))
      (node (ref "U$2") (pin "26") (pinfunction "26-SPI-CE1-N_26") (pintype "bidirectional"))
    )
    (net (code "69") (name "VCC") (class "Default")
      (node (ref "74HC595") (pin "10") (pinfunction "SCL_10") (pintype "input"))
      (node (ref "74HC595") (pin "16") (pinfunction "VCC_16") (pintype "power_in"))
      (node (ref "C3") (pin "1") (pinfunction "1_1") (pintype "passive"))
      (node (ref "C5") (pin "1") (pinfunction "1_1") (pintype "passive"))
      (node (ref "EXTOUT1") (pin "8") (pinfunction "8_8") (pintype "passive"))
      (node (ref "JP2") (pin "13") (pinfunction "13_13") (pintype "passive"))
      (node (ref "JP6") (pin "1") (pinfunction "1_1") (pintype "passive"))
      (node (ref "JP6") (pin "2") (pinfunction "2_2") (pintype "passive"))
      (node (ref "JP6") (pin "3") (pinfunction "3_3") (pintype "passive"))
      (node (ref "JP6") (pin "4") (pinfunction "4_4") (pintype "passive"))
      (node (ref "JP6") (pin "5") (pinfunction "5_5") (pintype "passive"))
      (node (ref "PCF8591") (pin "14") (pinfunction "VREF_14") (pintype "input"))
      (node (ref "PCF8591") (pin "16") (pinfunction "VDD_16") (pintype "power_in"))
      (node (ref "ROE") (pin "2") (pinfunction "2_2") (pintype "passive"))
      (node (ref "RP") (pin "2") (pinfunction "2_2") (pintype "passive"))
      (node (ref "U$2") (pin "1") (pinfunction "1-+3V3_1") (pintype "bidirectional"))
    )
    (net (code "70") (name "unconnected-(DS1307-SQW{slash}OUT-Pad7)") (class "Default")
      (node (ref "DS1307") (pin "7") (pinfunction "SQW/OUT_7") (pintype "bidirectional"))
    )
    (net (code "71") (name "unconnected-(PCF8591-OSC-Pad11)") (class "Default")
      (node (ref "PCF8591") (pin "11") (pinfunction "OSC_11") (pintype "input"))
    )
    (net (code "72") (name "unconnected-(T1-M2-4-Pad4)") (class "Default")
      (node (ref "T1") (pin "4") (pinfunction "M2-4_4") (pintype "bidirectional"))
    )
    (net (code "73") (name "unconnected-(T2-M2-4-Pad4)") (class "Default")
      (node (ref "T2") (pin "4") (pinfunction "M2-4_4") (pintype "bidirectional"))
    )
    (net (code "74") (name "unconnected-(T3-M2-4-Pad4)") (class "Default")
      (node (ref "T3") (pin "4") (pinfunction "M2-4_4") (pintype "bidirectional"))
    )
    (net (code "75") (name "unconnected-(T4-M2-4-Pad4)") (class "Default")
      (node (ref "T4") (pin "4") (pinfunction "M2-4_4") (pintype "bidirectional"))
    )
    (net (code "76") (name "unconnected-(T5-M2-4-Pad4)") (class "Default")
      (node (ref "T5") (pin "4") (pinfunction "M2-4_4") (pintype "bidirectional"))
    )
    (net (code "77") (name "unconnected-(T6-M2-4-Pad4)") (class "Default")
      (node (ref "T6") (pin "4") (pinfunction "M2-4_4") (pintype "bidirectional"))
    )
    (net (code "78") (name "unconnected-(T7-M2-4-Pad4)") (class "Default")
      (node (ref "T7") (pin "4") (pinfunction "M2-4_4") (pintype "bidirectional"))
    )
    (net (code "79") (name "unconnected-(T8-M2-4-Pad4)") (class "Default")
      (node (ref "T8") (pin "4") (pinfunction "M2-4_4") (pintype "bidirectional"))
    )
  )
)
